# converter.net
KiCad netlist of a schematic drawn in Altium Designer
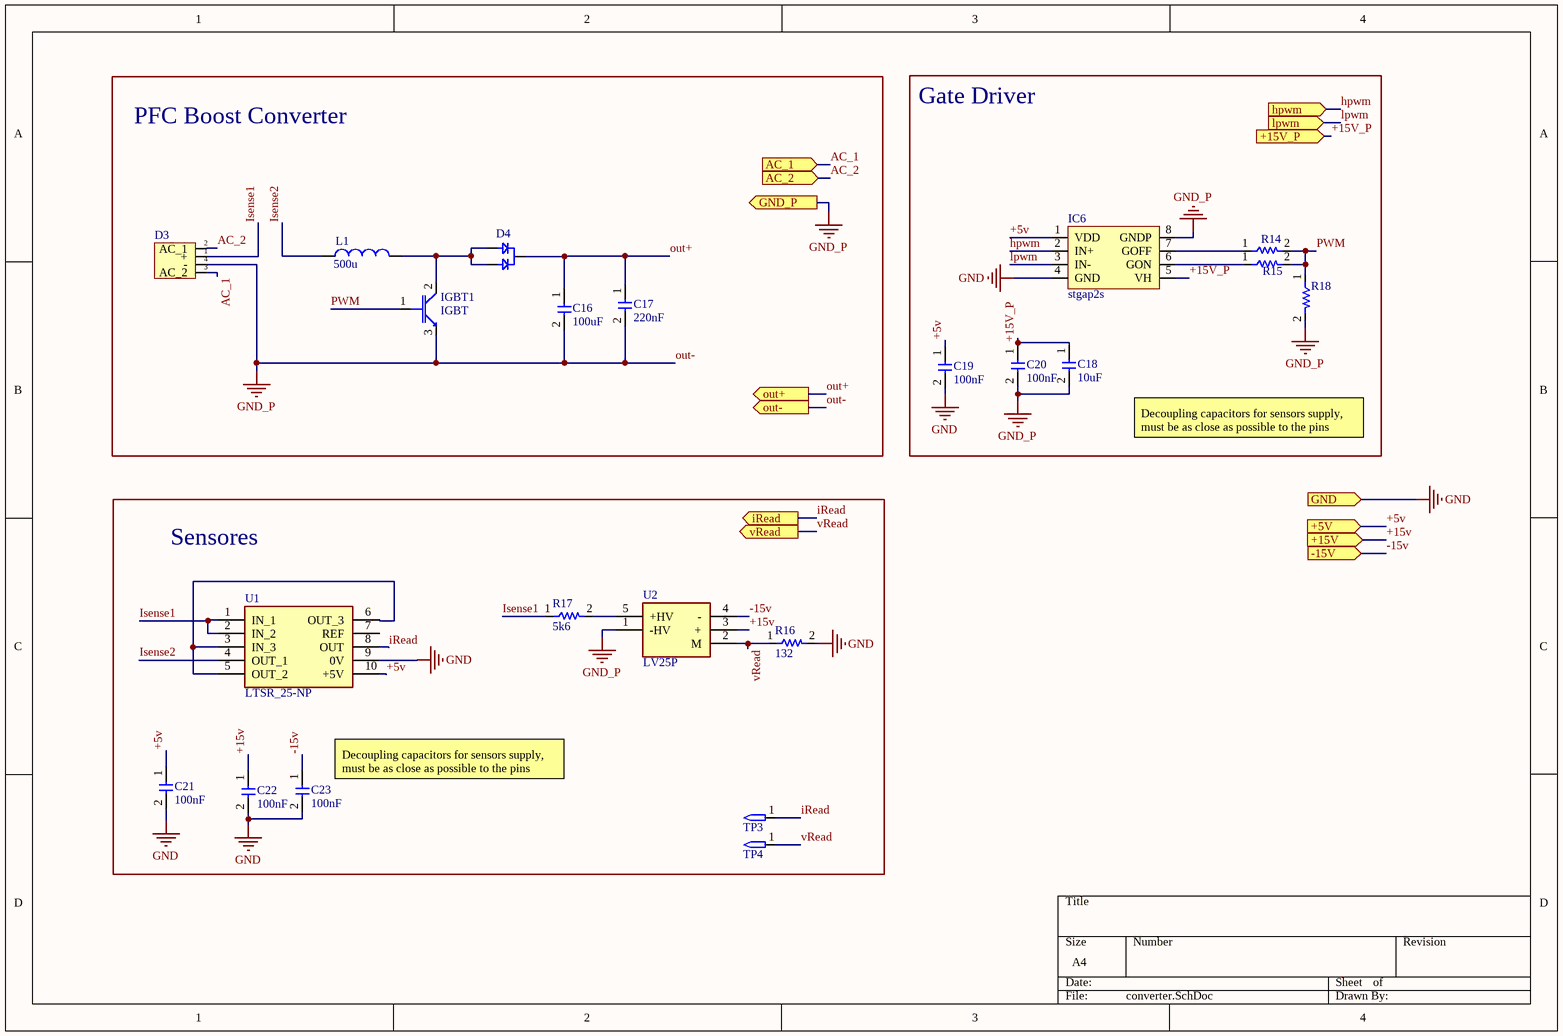
[diagram p0: converter.SchDoc]

(export (version "E")
  (design (tool "Eeschema 10.0.6"))
  (components
    (comp (ref "C16")
      (value "100uF")
      (footprint "CAP 20x12.5")
      (libsource (lib "Schlib1") (part "Capacitor"))
    )
    (comp (ref "C17")
      (value "220nF")
      (footprint "CAPACITOR 220nF")
      (libsource (lib "Schlib1") (part "Capacitor"))
    )
    (comp (ref "C18")
      (value "10uF")
      (footprint "CAPACITOR_0805")
      (libsource (lib "Schlib1") (part "Capacitor"))
    )
    (comp (ref "C19")
      (value "100nF")
      (footprint "CAPACITOR_0805")
      (libsource (lib "Schlib1") (part "Capacitor"))
    )
    (comp (ref "C20")
      (value "100nF")
      (footprint "CAPACITOR_0805")
      (libsource (lib "Schlib1") (part "Capacitor"))
    )
    (comp (ref "C21")
      (value "100nF")
      (footprint "CAPACITOR_0805")
      (libsource (lib "Schlib1") (part "Capacitor"))
    )
    (comp (ref "C22")
      (value "100nF")
      (footprint "CAPACITOR_0805")
      (libsource (lib "Schlib1") (part "Capacitor"))
    )
    (comp (ref "C23")
      (value "100nF")
      (footprint "CAPACITOR_0805")
      (libsource (lib "Schlib1") (part "Capacitor"))
    )
    (comp (ref "D3")
      (value "rectifierBridge")
      (footprint "GBI10M")
      (libsource (lib "Schlib1") (part "rectifierBridge"))
    )
    (comp (ref "D4") (value "Diode dual") (footprint "D2PAK") (libsource (lib "Schlib1") (part "Diode dual")))
    (comp (ref "IC6") (value "stgap2s") (footprint "SO-8") (libsource (lib "Schlib1") (part "stgap2s")))
    (comp (ref "IGBT1") (value "IGBT") (footprint "D2PAK") (libsource (lib "Schlib1") (part "IGBT")))
    (comp (ref "L1")
      (value "500u")
      (footprint "INDUCTOR 500u")
      (description "Inductor")
      (libsource (lib "Simulation Generic Components") (part "Inductor"))
    )
    (comp (ref "R14")
      (value "Resistor")
      (footprint "RESISTOR_0805")
      (libsource (lib "Schlib1") (part "Resistor"))
    )
    (comp (ref "R15")
      (value "Resistor")
      (footprint "RESISTOR_0805")
      (libsource (lib "Schlib1") (part "Resistor"))
    )
    (comp (ref "R16")
      (value "132")
      (footprint "RESISTOR_0805")
      (description "82.5 mW")
      (libsource (lib "Schlib1") (part "Resistor"))
    )
    (comp (ref "R17")
      (value "5k6")
      (footprint "RESISTOR_0805")
      (description "140 mW")
      (libsource (lib "Schlib1") (part "Resistor"))
    )
    (comp (ref "R18")
      (value "Resistor")
      (footprint "RESISTOR_0805")
      (libsource (lib "Schlib1") (part "Resistor"))
    )
    (comp (ref "TP3")
      (value "TestPoint")
      (footprint "TestPoint")
      (libsource (lib "Schlib1") (part "TestPoint"))
    )
    (comp (ref "TP4")
      (value "TestPoint")
      (footprint "TestPoint")
      (libsource (lib "Schlib1") (part "TestPoint"))
    )
    (comp (ref "U1")
      (value "LTSR_25-NP")
      (footprint "LTSR25-NP")
      (description "Undefined or Miscellaneous")
      (fields (field (name "MANUFACTURER_PART_NUMBER") "LTSR 25-NP"))
      (libsource (lib "Schlib1") (part "LTSR_25-NP"))
    )
    (comp (ref "U2")
      (value "LV25P")
      (footprint "LV-25-P/LV-20-P")
      (description "Undefined or Miscellaneous")
      (libsource (lib "Schlib1") (part "LV25P"))
    )
  )
  (nets
    (net (code "1") (name "/+5v") (class "Default")
      (node (ref "C19") (pin "1") (pinfunction "1_1") (pintype "passive"))
      (node (ref "C21") (pin "1") (pinfunction "1_1") (pintype "passive"))
      (node (ref "IC6") (pin "1") (pinfunction "VDD_1") (pintype "passive"))
      (node (ref "U1") (pin "10") (pinfunction "+5V_10") (pintype "passive"))
    )
    (net (code "2") (name "/+15V_P") (class "Default")
      (node (ref "C18") (pin "1") (pinfunction "1_1") (pintype "passive"))
      (node (ref "C20") (pin "1") (pinfunction "1_1") (pintype "passive"))
      (node (ref "IC6") (pin "5") (pinfunction "VH_5") (pintype "passive"))
    )
    (net (code "3") (name "/+15v") (class "Default")
      (node (ref "C22") (pin "1") (pinfunction "1_1") (pintype "passive"))
      (node (ref "U2") (pin "3") (pinfunction "+_3") (pintype "passive"))
    )
    (net (code "4") (name "/-15v") (class "Default")
      (node (ref "C23") (pin "1") (pinfunction "1_1") (pintype "passive"))
      (node (ref "U2") (pin "4") (pinfunction "-_4") (pintype "passive"))
    )
    (net (code "5") (name "/AC_1") (class "Default")
      (node (ref "D3") (pin "3") (pinfunction "AC_2_3") (pintype "passive"))
    )
    (net (code "6") (name "/AC_2") (class "Default")
      (node (ref "D3") (pin "2") (pinfunction "AC_1_2") (pintype "passive"))
    )
    (net (code "7") (name "/Isense1") (class "Default")
      (node (ref "D3") (pin "1") (pinfunction "+_1") (pintype "passive"))
      (node (ref "R17") (pin "1") (pinfunction "6_1") (pintype "passive"))
      (node (ref "U1") (pin "1") (pinfunction "IN_1_1") (pintype "passive"))
      (node (ref "U1") (pin "2") (pinfunction "IN_2_2") (pintype "passive"))
    )
    (net (code "8") (name "/Isense2") (class "Default")
      (node (ref "L1") (pin "1") (pinfunction "1_1") (pintype "passive"))
      (node (ref "U1") (pin "4") (pinfunction "OUT_1_4") (pintype "passive"))
    )
    (net (code "9") (name "/PWM") (class "Default")
      (node (ref "IGBT1") (pin "1") (pintype "passive"))
      (node (ref "R14") (pin "2") (pinfunction "2_2") (pintype "passive"))
      (node (ref "R15") (pin "2") (pinfunction "2_2") (pintype "passive"))
      (node (ref "R18") (pin "1") (pinfunction "6_1") (pintype "passive"))
    )
    (net (code "10") (name "/hpwm") (class "Default")
      (node (ref "IC6") (pin "2") (pinfunction "IN+_2") (pintype "passive"))
    )
    (net (code "11") (name "/iRead") (class "Default")
      (node (ref "TP3") (pin "1") (pinfunction "1_1") (pintype "passive"))
      (node (ref "U1") (pin "8") (pinfunction "OUT_8") (pintype "passive"))
    )
    (net (code "12") (name "/lpwm") (class "Default")
      (node (ref "IC6") (pin "3") (pinfunction "IN-_3") (pintype "passive"))
    )
    (net (code "13") (name "/out+") (class "Default")
      (node (ref "C16") (pin "1") (pinfunction "1_1") (pintype "passive"))
      (node (ref "C17") (pin "1") (pinfunction "1_1") (pintype "passive"))
      (node (ref "D4") (pin "2") (pinfunction "2_2") (pintype "passive"))
    )
    (net (code "14") (name "/vRead") (class "Default")
      (node (ref "R16") (pin "1") (pinfunction "6_1") (pintype "passive"))
      (node (ref "TP4") (pin "1") (pinfunction "1_1") (pintype "passive"))
      (node (ref "U2") (pin "2") (pinfunction "M_2") (pintype "passive"))
    )
    (net (code "15") (name "GND") (class "Default")
      (node (ref "C19") (pin "2") (pinfunction "2_2") (pintype "passive"))
      (node (ref "C21") (pin "2") (pinfunction "2_2") (pintype "passive"))
      (node (ref "C22") (pin "2") (pinfunction "2_2") (pintype "passive"))
      (node (ref "C23") (pin "2") (pinfunction "2_2") (pintype "passive"))
      (node (ref "IC6") (pin "4") (pinfunction "GND_4") (pintype "passive"))
      (node (ref "R16") (pin "2") (pinfunction "2_2") (pintype "passive"))
      (node (ref "U1") (pin "9") (pinfunction "0V_9") (pintype "passive"))
    )
    (net (code "16") (name "GND_P") (class "Default")
      (node (ref "C16") (pin "2") (pinfunction "2_2") (pintype "passive"))
      (node (ref "C17") (pin "2") (pinfunction "2_2") (pintype "passive"))
      (node (ref "C18") (pin "2") (pinfunction "2_2") (pintype "passive"))
      (node (ref "C20") (pin "2") (pinfunction "2_2") (pintype "passive"))
      (node (ref "D3") (pin "4") (pinfunction "-_4") (pintype "passive"))
      (node (ref "IC6") (pin "8") (pinfunction "GNDP_8") (pintype "passive"))
      (node (ref "IGBT1") (pin "3") (pintype "passive"))
      (node (ref "R18") (pin "2") (pinfunction "2_2") (pintype "passive"))
      (node (ref "U2") (pin "1") (pinfunction "-HV_1") (pintype "passive"))
    )
    (net (code "17") (name "Net-(D4-Pad1)") (class "Default")
      (node (ref "D4") (pin "1") (pinfunction "1_1") (pintype "passive"))
      (node (ref "D4") (pin "3") (pinfunction "3_3") (pintype "passive"))
      (node (ref "IGBT1") (pin "2") (pintype "passive"))
      (node (ref "L1") (pin "2") (pinfunction "2_2") (pintype "passive"))
    )
    (net (code "18") (name "Net-(IC6-GOFF)") (class "Default")
      (node (ref "IC6") (pin "7") (pinfunction "GOFF_7") (pintype "passive"))
      (node (ref "R14") (pin "1") (pinfunction "6_1") (pintype "passive"))
    )
    (net (code "19") (name "Net-(IC6-GON)") (class "Default")
      (node (ref "IC6") (pin "6") (pinfunction "GON_6") (pintype "passive"))
      (node (ref "R15") (pin "1") (pinfunction "6_1") (pintype "passive"))
    )
    (net (code "20") (name "Net-(U1-IN_3)") (class "Default")
      (node (ref "U1") (pin "3") (pinfunction "IN_3_3") (pintype "passive"))
      (node (ref "U1") (pin "5") (pinfunction "OUT_2_5") (pintype "passive"))
      (node (ref "U1") (pin "6") (pinfunction "OUT_3_6") (pintype "passive"))
    )
    (net (code "21") (name "Net-(U2-+HV)") (class "Default")
      (node (ref "R17") (pin "2") (pinfunction "2_2") (pintype "passive"))
      (node (ref "U2") (pin "5") (pinfunction "+HV_5") (pintype "passive"))
    )
    (net (code "22") (name "unconnected-(U1-REF-Pad7)") (class "Default")
      (node (ref "U1") (pin "7") (pinfunction "REF_7") (pintype "passive"))
    )
  )
)
